# design.net
KiCad netlist of a schematic drawn in Altium Designer
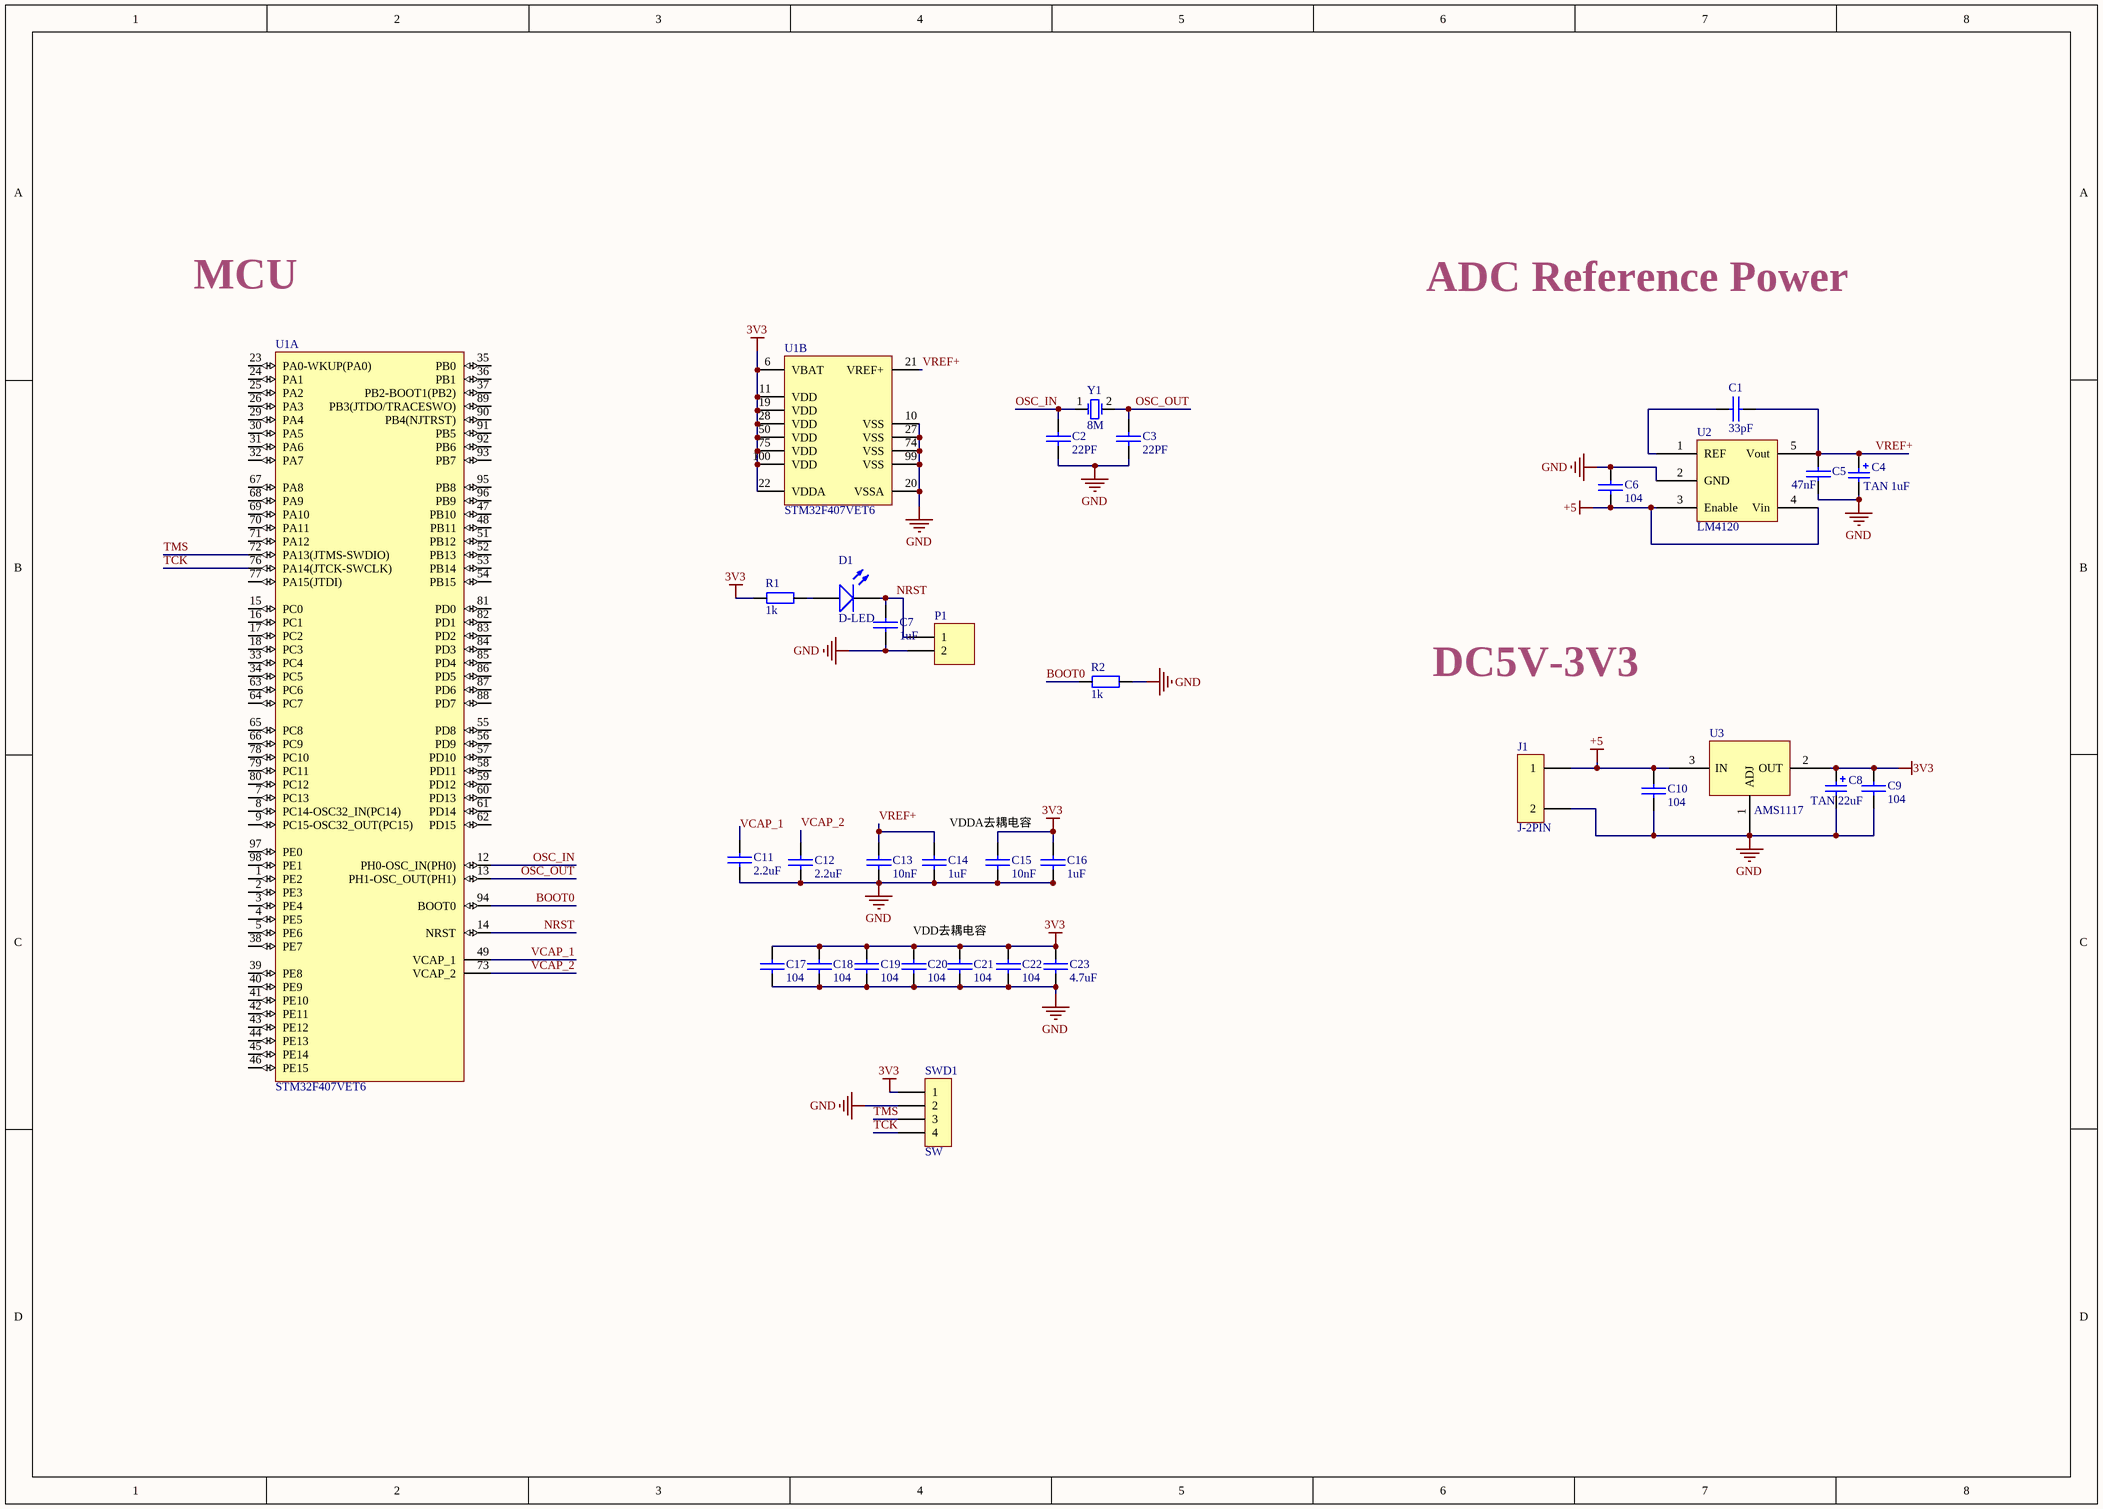
[diagram p0: 更新版.SchDoc]

(export (version "E")
  (design (tool "Eeschema 10.0.6"))
  (components
    (comp (ref "C1")
      (value "33pF")
      (footprint "C-0603")
      (description "MLCC")
      (libsource (lib "ACTION_SchematicDiagramPack") (part "C"))
    )
    (comp (ref "C2")
      (value "22PF")
      (footprint "C-0603")
      (description "MLCC")
      (libsource (lib "ACTION_SchematicDiagramPack") (part "C"))
    )
    (comp (ref "C3")
      (value "22PF")
      (footprint "C-0603")
      (description "MLCC")
      (libsource (lib "ACTION_SchematicDiagramPack") (part "C"))
    )
    (comp (ref "C4")
      (value "TAN 1uF")
      (footprint "CAP-Ta-1206")
      (description "Tantalum Capacitors")
      (libsource (lib "ACTION_SchematicDiagramPack") (part "C-TAN"))
    )
    (comp (ref "C5")
      (value "47nF")
      (footprint "C-0603")
      (description "MLCC")
      (libsource (lib "ACTION_SchematicDiagramPack") (part "C"))
    )
    (comp (ref "C6")
      (value "104")
      (footprint "C-0603")
      (description "MLCC")
      (libsource (lib "ACTION_SchematicDiagramPack") (part "C"))
    )
    (comp (ref "C7")
      (value "1uF")
      (footprint "C-0603")
      (description "MLCC")
      (libsource (lib "ACTION_SchematicDiagramPack") (part "C"))
    )
    (comp (ref "C8")
      (value "TAN 22uF")
      (footprint "CAP-Ta-1206")
      (description "Tantalum Capacitors")
      (libsource (lib "ACTION_SchematicDiagramPack") (part "C-TAN"))
    )
    (comp (ref "C9")
      (value "104")
      (footprint "C-0603")
      (description "MLCC")
      (libsource (lib "ACTION_SchematicDiagramPack") (part "C"))
    )
    (comp (ref "C10")
      (value "104")
      (footprint "C-0603")
      (description "MLCC")
      (libsource (lib "ACTION_SchematicDiagramPack") (part "C"))
    )
    (comp (ref "C11")
      (value "2.2uF")
      (footprint "C-0603")
      (description "MLCC")
      (libsource (lib "ACTION_SchematicDiagramPack") (part "C"))
    )
    (comp (ref "C12")
      (value "2.2uF")
      (footprint "C-0603")
      (description "MLCC")
      (libsource (lib "ACTION_SchematicDiagramPack") (part "C"))
    )
    (comp (ref "C13")
      (value "10nF")
      (footprint "C-0603")
      (description "MLCC")
      (libsource (lib "ACTION_SchematicDiagramPack") (part "C"))
    )
    (comp (ref "C14")
      (value "1uF")
      (footprint "C-0603")
      (description "MLCC")
      (libsource (lib "ACTION_SchematicDiagramPack") (part "C"))
    )
    (comp (ref "C15")
      (value "10nF")
      (footprint "C-0603")
      (description "MLCC")
      (libsource (lib "ACTION_SchematicDiagramPack") (part "C"))
    )
    (comp (ref "C16")
      (value "1uF")
      (footprint "C-0603")
      (description "MLCC")
      (libsource (lib "ACTION_SchematicDiagramPack") (part "C"))
    )
    (comp (ref "C17")
      (value "104")
      (footprint "C-0603")
      (description "MLCC")
      (libsource (lib "ACTION_SchematicDiagramPack") (part "C"))
    )
    (comp (ref "C18")
      (value "104")
      (footprint "C-0603")
      (description "MLCC")
      (libsource (lib "ACTION_SchematicDiagramPack") (part "C"))
    )
    (comp (ref "C19")
      (value "104")
      (footprint "C-0603")
      (description "MLCC")
      (libsource (lib "ACTION_SchematicDiagramPack") (part "C"))
    )
    (comp (ref "C20")
      (value "104")
      (footprint "C-0603")
      (description "MLCC")
      (libsource (lib "ACTION_SchematicDiagramPack") (part "C"))
    )
    (comp (ref "C21")
      (value "104")
      (footprint "C-0603")
      (description "MLCC")
      (libsource (lib "ACTION_SchematicDiagramPack") (part "C"))
    )
    (comp (ref "C22")
      (value "104")
      (footprint "C-0603")
      (description "MLCC")
      (libsource (lib "ACTION_SchematicDiagramPack") (part "C"))
    )
    (comp (ref "C23")
      (value "4.7uF")
      (footprint "C-0603")
      (description "MLCC")
      (libsource (lib "ACTION_SchematicDiagramPack") (part "C"))
    )
    (comp (ref "D1")
      (value "D-LED")
      (footprint "D-LED-0603")
      (description "LED")
      (libsource (lib "ACTION_SchematicDiagramPack") (part "D-LED"))
    )
    (comp (ref "J1")
      (value "J-2PIN")
      (footprint "J-XH-2A")
      (libsource (lib "ACTION_SchematicDiagramPack") (part "J-2PIN"))
    )
    (comp (ref "P1")
      (value "~")
      (footprint "按键两脚")
      (description "Header, 2-Pin")
      (fields (field (name "PUBLISHER") "Altium Limited"))
      (libsource (lib "Miscellaneous Connectors") (part "Header 2"))
    )
    (comp (ref "R1")
      (value "1k")
      (footprint "R-0603")
      (description "Resistor")
      (libsource (lib "ACTION_SchematicDiagramPack") (part "R"))
    )
    (comp (ref "R2")
      (value "1k")
      (footprint "R-0603")
      (description "Resistor")
      (libsource (lib "ACTION_SchematicDiagramPack") (part "R"))
    )
    (comp (ref "SWD1")
      (value "SW")
      (footprint "J-1.27-4P")
      (fields (field (name "PUBLISHER") "Altium Limited"))
      (libsource (lib "ACTION_SchematicDiagramPack") (part "J-4PIN"))
    )
    (comp (ref "U1")
      (value "STM32F407VET6")
      (footprint "STM-LQFP100_M")
      (libsource (lib "ACTION_SchematicDiagramPack") (part "STM32F407VET6"))
    )
    (comp (ref "U2")
      (value "LM4120")
      (footprint "SOT-235")
      (description "基准电压IC")
      (libsource (lib "ACTION_SchematicDiagramPack") (part "LM4120"))
    )
    (comp (ref "U3")
      (value "AMS1117")
      (footprint "SOT-223")
      (description "LDO")
      (libsource (lib "ACTION_SchematicDiagramPack") (part "AMS1117"))
    )
    (comp (ref "Y1")
      (value "8M")
      (footprint "X-HC49S")
      (description "Crystal Oscillator")
      (fields (field (name "PUBLISHER") "Altium Limited"))
      (libsource (lib "ACTION_SchematicDiagramPack") (part "Crystal"))
    )
  )
  (nets
    (net (code "1") (name "+5") (class "Default")
      (node (ref "C10") (pin "1") (pinfunction "1_1") (pintype "passive"))
      (node (ref "C6") (pin "2") (pinfunction "2_2") (pintype "passive"))
      (node (ref "J1") (pin "1") (pinfunction "1_1") (pintype "passive"))
      (node (ref "U2") (pin "3") (pinfunction "Enable_3") (pintype "passive"))
      (node (ref "U2") (pin "4") (pinfunction "Vin_4") (pintype "passive"))
      (node (ref "U3") (pin "3") (pinfunction "IN_3") (pintype "passive"))
    )
    (net (code "2") (name "/BOOT0") (class "Default")
      (node (ref "R2") (pin "1") (pintype "passive"))
      (node (ref "U1") (pin "94") (pinfunction "BOOT0_94") (pintype "bidirectional"))
    )
    (net (code "3") (name "/NRST") (class "Default")
      (node (ref "C7") (pin "2") (pinfunction "2_2") (pintype "passive"))
      (node (ref "D1") (pin "K") (pinfunction "K_K") (pintype "passive"))
      (node (ref "P1") (pin "1") (pinfunction "1_1") (pintype "passive"))
      (node (ref "U1") (pin "14") (pinfunction "NRST_14") (pintype "bidirectional"))
    )
    (net (code "4") (name "/OSC_IN") (class "Default")
      (node (ref "C2") (pin "1") (pinfunction "1_1") (pintype "passive"))
      (node (ref "U1") (pin "12") (pinfunction "PH0-OSC_IN(PH0)_12") (pintype "bidirectional"))
      (node (ref "Y1") (pin "1") (pinfunction "OSC1_1") (pintype "passive"))
    )
    (net (code "5") (name "/OSC_OUT") (class "Default")
      (node (ref "C3") (pin "1") (pinfunction "1_1") (pintype "passive"))
      (node (ref "U1") (pin "13") (pinfunction "PH1-OSC_OUT(PH1)_13") (pintype "bidirectional"))
      (node (ref "Y1") (pin "2") (pinfunction "OSC2_2") (pintype "passive"))
    )
    (net (code "6") (name "/TCK") (class "Default")
      (node (ref "SWD1") (pin "4") (pinfunction "4_4") (pintype "passive"))
      (node (ref "U1") (pin "76") (pinfunction "PA14(JTCK-SWCLK)_76") (pintype "bidirectional"))
    )
    (net (code "7") (name "/TMS") (class "Default")
      (node (ref "SWD1") (pin "3") (pinfunction "3_3") (pintype "passive"))
      (node (ref "U1") (pin "72") (pinfunction "PA13(JTMS-SWDIO)_72") (pintype "bidirectional"))
    )
    (net (code "8") (name "/VCAP_1") (class "Default")
      (node (ref "C11") (pin "2") (pinfunction "2_2") (pintype "passive"))
      (node (ref "U1") (pin "49") (pinfunction "VCAP_1_49") (pintype "power_in"))
    )
    (net (code "9") (name "/VCAP_2") (class "Default")
      (node (ref "C12") (pin "2") (pinfunction "2_2") (pintype "passive"))
      (node (ref "U1") (pin "73") (pinfunction "VCAP_2_73") (pintype "power_in"))
    )
    (net (code "10") (name "/VREF+") (class "Default")
      (node (ref "C1") (pin "2") (pinfunction "2_2") (pintype "passive"))
      (node (ref "C13") (pin "2") (pinfunction "2_2") (pintype "passive"))
      (node (ref "C14") (pin "2") (pinfunction "2_2") (pintype "passive"))
      (node (ref "C4") (pin "1") (pinfunction "1_1") (pintype "passive"))
      (node (ref "C5") (pin "1") (pinfunction "1_1") (pintype "passive"))
      (node (ref "U1") (pin "21") (pinfunction "VREF+_21") (pintype "power_in"))
      (node (ref "U2") (pin "5") (pinfunction "Vout_5") (pintype "passive"))
    )
    (net (code "11") (name "3V3") (class "Default")
      (node (ref "C15") (pin "2") (pinfunction "2_2") (pintype "passive"))
      (node (ref "C16") (pin "2") (pinfunction "2_2") (pintype "passive"))
      (node (ref "C17") (pin "2") (pinfunction "2_2") (pintype "passive"))
      (node (ref "C18") (pin "2") (pinfunction "2_2") (pintype "passive"))
      (node (ref "C19") (pin "2") (pinfunction "2_2") (pintype "passive"))
      (node (ref "C20") (pin "2") (pinfunction "2_2") (pintype "passive"))
      (node (ref "C21") (pin "2") (pinfunction "2_2") (pintype "passive"))
      (node (ref "C22") (pin "2") (pinfunction "2_2") (pintype "passive"))
      (node (ref "C23") (pin "2") (pinfunction "2_2") (pintype "passive"))
      (node (ref "C8") (pin "1") (pinfunction "1_1") (pintype "passive"))
      (node (ref "C9") (pin "1") (pinfunction "1_1") (pintype "passive"))
      (node (ref "R1") (pin "1") (pintype "passive"))
      (node (ref "SWD1") (pin "1") (pinfunction "1_1") (pintype "passive"))
      (node (ref "U1") (pin "100") (pinfunction "VDD_100") (pintype "power_in"))
      (node (ref "U1") (pin "11") (pinfunction "VDD_11") (pintype "power_in"))
      (node (ref "U1") (pin "19") (pinfunction "VDD_19") (pintype "power_in"))
      (node (ref "U1") (pin "22") (pinfunction "VDDA_22") (pintype "power_in"))
      (node (ref "U1") (pin "28") (pinfunction "VDD_28") (pintype "power_in"))
      (node (ref "U1") (pin "50") (pinfunction "VDD_50") (pintype "power_in"))
      (node (ref "U1") (pin "6") (pinfunction "VBAT_6") (pintype "power_in"))
      (node (ref "U1") (pin "75") (pinfunction "VDD_75") (pintype "power_in"))
      (node (ref "U3") (pin "2") (pinfunction "OUT_2") (pintype "passive"))
    )
    (net (code "12") (name "GND") (class "Default")
      (node (ref "C10") (pin "2") (pinfunction "2_2") (pintype "passive"))
      (node (ref "C11") (pin "1") (pinfunction "1_1") (pintype "passive"))
      (node (ref "C12") (pin "1") (pinfunction "1_1") (pintype "passive"))
      (node (ref "C13") (pin "1") (pinfunction "1_1") (pintype "passive"))
      (node (ref "C14") (pin "1") (pinfunction "1_1") (pintype "passive"))
      (node (ref "C15") (pin "1") (pinfunction "1_1") (pintype "passive"))
      (node (ref "C16") (pin "1") (pinfunction "1_1") (pintype "passive"))
      (node (ref "C17") (pin "1") (pinfunction "1_1") (pintype "passive"))
      (node (ref "C18") (pin "1") (pinfunction "1_1") (pintype "passive"))
      (node (ref "C19") (pin "1") (pinfunction "1_1") (pintype "passive"))
      (node (ref "C2") (pin "2") (pinfunction "2_2") (pintype "passive"))
      (node (ref "C20") (pin "1") (pinfunction "1_1") (pintype "passive"))
      (node (ref "C21") (pin "1") (pinfunction "1_1") (pintype "passive"))
      (node (ref "C22") (pin "1") (pinfunction "1_1") (pintype "passive"))
      (node (ref "C23") (pin "1") (pinfunction "1_1") (pintype "passive"))
      (node (ref "C3") (pin "2") (pinfunction "2_2") (pintype "passive"))
      (node (ref "C4") (pin "2") (pinfunction "2_2") (pintype "passive"))
      (node (ref "C5") (pin "2") (pinfunction "2_2") (pintype "passive"))
      (node (ref "C6") (pin "1") (pinfunction "1_1") (pintype "passive"))
      (node (ref "C7") (pin "1") (pinfunction "1_1") (pintype "passive"))
      (node (ref "C8") (pin "2") (pinfunction "2_2") (pintype "passive"))
      (node (ref "C9") (pin "2") (pinfunction "2_2") (pintype "passive"))
      (node (ref "J1") (pin "2") (pinfunction "2_2") (pintype "passive"))
      (node (ref "P1") (pin "2") (pinfunction "2_2") (pintype "passive"))
      (node (ref "R2") (pin "2") (pintype "passive"))
      (node (ref "SWD1") (pin "2") (pinfunction "2_2") (pintype "passive"))
      (node (ref "U1") (pin "10") (pinfunction "VSS_10") (pintype "power_in"))
      (node (ref "U1") (pin "20") (pinfunction "VSSA_20") (pintype "power_in"))
      (node (ref "U1") (pin "27") (pinfunction "VSS_27") (pintype "power_in"))
      (node (ref "U1") (pin "74") (pinfunction "VSS_74") (pintype "power_in"))
      (node (ref "U1") (pin "99") (pinfunction "VSS_99") (pintype "power_in"))
      (node (ref "U2") (pin "2") (pinfunction "GND_2") (pintype "passive"))
      (node (ref "U3") (pin "1") (pinfunction "ADJ_1") (pintype "passive"))
    )
    (net (code "13") (name "Net-(D1-PadA)") (class "Default")
      (node (ref "D1") (pin "A") (pinfunction "A_A") (pintype "passive"))
      (node (ref "R1") (pin "2") (pintype "passive"))
    )
    (net (code "14") (name "Net-(U2-REF)") (class "Default")
      (node (ref "C1") (pin "1") (pinfunction "1_1") (pintype "passive"))
      (node (ref "U2") (pin "1") (pinfunction "REF_1") (pintype "passive"))
    )
    (net (code "15") (name "unconnected-(U1A-PA0-WKUP(PA0)-Pad23)") (class "Default")
      (node (ref "U1") (pin "23") (pinfunction "PA0-WKUP(PA0)_23") (pintype "bidirectional"))
    )
    (net (code "16") (name "unconnected-(U1A-PA1-Pad24)") (class "Default")
      (node (ref "U1") (pin "24") (pinfunction "PA1_24") (pintype "bidirectional"))
    )
    (net (code "17") (name "unconnected-(U1A-PA2-Pad25)") (class "Default")
      (node (ref "U1") (pin "25") (pinfunction "PA2_25") (pintype "bidirectional"))
    )
    (net (code "18") (name "unconnected-(U1A-PA3-Pad26)") (class "Default")
      (node (ref "U1") (pin "26") (pinfunction "PA3_26") (pintype "bidirectional"))
    )
    (net (code "19") (name "unconnected-(U1A-PA4-Pad29)") (class "Default")
      (node (ref "U1") (pin "29") (pinfunction "PA4_29") (pintype "bidirectional"))
    )
    (net (code "20") (name "unconnected-(U1A-PA5-Pad30)") (class "Default")
      (node (ref "U1") (pin "30") (pinfunction "PA5_30") (pintype "bidirectional"))
    )
    (net (code "21") (name "unconnected-(U1A-PA6-Pad31)") (class "Default")
      (node (ref "U1") (pin "31") (pinfunction "PA6_31") (pintype "bidirectional"))
    )
    (net (code "22") (name "unconnected-(U1A-PA7-Pad32)") (class "Default")
      (node (ref "U1") (pin "32") (pinfunction "PA7_32") (pintype "bidirectional"))
    )
    (net (code "23") (name "unconnected-(U1A-PA8-Pad67)") (class "Default")
      (node (ref "U1") (pin "67") (pinfunction "PA8_67") (pintype "bidirectional"))
    )
    (net (code "24") (name "unconnected-(U1A-PA9-Pad68)") (class "Default")
      (node (ref "U1") (pin "68") (pinfunction "PA9_68") (pintype "bidirectional"))
    )
    (net (code "25") (name "unconnected-(U1A-PA10-Pad69)") (class "Default")
      (node (ref "U1") (pin "69") (pinfunction "PA10_69") (pintype "bidirectional"))
    )
    (net (code "26") (name "unconnected-(U1A-PA11-Pad70)") (class "Default")
      (node (ref "U1") (pin "70") (pinfunction "PA11_70") (pintype "bidirectional"))
    )
    (net (code "27") (name "unconnected-(U1A-PA12-Pad71)") (class "Default")
      (node (ref "U1") (pin "71") (pinfunction "PA12_71") (pintype "bidirectional"))
    )
    (net (code "28") (name "unconnected-(U1A-PA15(JTDI)-Pad77)") (class "Default")
      (node (ref "U1") (pin "77") (pinfunction "PA15(JTDI)_77") (pintype "bidirectional"))
    )
    (net (code "29") (name "unconnected-(U1A-PB0-Pad35)") (class "Default")
      (node (ref "U1") (pin "35") (pinfunction "PB0_35") (pintype "bidirectional"))
    )
    (net (code "30") (name "unconnected-(U1A-PB1-Pad36)") (class "Default")
      (node (ref "U1") (pin "36") (pinfunction "PB1_36") (pintype "bidirectional"))
    )
    (net (code "31") (name "unconnected-(U1A-PB2-BOOT1(PB2)-Pad37)") (class "Default")
      (node (ref "U1") (pin "37") (pinfunction "PB2-BOOT1(PB2)_37") (pintype "bidirectional"))
    )
    (net (code "32") (name "unconnected-(U1A-PB3(JTDO{slash}TRACESWO)-Pad89)") (class "Default")
      (node (ref "U1") (pin "89") (pinfunction "PB3(JTDO/TRACESWO)_89") (pintype "bidirectional"))
    )
    (net (code "33") (name "unconnected-(U1A-PB4(NJTRST)-Pad90)") (class "Default")
      (node (ref "U1") (pin "90") (pinfunction "PB4(NJTRST)_90") (pintype "bidirectional"))
    )
    (net (code "34") (name "unconnected-(U1A-PB5-Pad91)") (class "Default")
      (node (ref "U1") (pin "91") (pinfunction "PB5_91") (pintype "bidirectional"))
    )
    (net (code "35") (name "unconnected-(U1A-PB6-Pad92)") (class "Default")
      (node (ref "U1") (pin "92") (pinfunction "PB6_92") (pintype "bidirectional"))
    )
    (net (code "36") (name "unconnected-(U1A-PB7-Pad93)") (class "Default")
      (node (ref "U1") (pin "93") (pinfunction "PB7_93") (pintype "bidirectional"))
    )
    (net (code "37") (name "unconnected-(U1A-PB8-Pad95)") (class "Default")
      (node (ref "U1") (pin "95") (pinfunction "PB8_95") (pintype "bidirectional"))
    )
    (net (code "38") (name "unconnected-(U1A-PB9-Pad96)") (class "Default")
      (node (ref "U1") (pin "96") (pinfunction "PB9_96") (pintype "bidirectional"))
    )
    (net (code "39") (name "unconnected-(U1A-PB10-Pad47)") (class "Default")
      (node (ref "U1") (pin "47") (pinfunction "PB10_47") (pintype "bidirectional"))
    )
    (net (code "40") (name "unconnected-(U1A-PB11-Pad48)") (class "Default")
      (node (ref "U1") (pin "48") (pinfunction "PB11_48") (pintype "bidirectional"))
    )
    (net (code "41") (name "unconnected-(U1A-PB12-Pad51)") (class "Default")
      (node (ref "U1") (pin "51") (pinfunction "PB12_51") (pintype "bidirectional"))
    )
    (net (code "42") (name "unconnected-(U1A-PB13-Pad52)") (class "Default")
      (node (ref "U1") (pin "52") (pinfunction "PB13_52") (pintype "bidirectional"))
    )
    (net (code "43") (name "unconnected-(U1A-PB14-Pad53)") (class "Default")
      (node (ref "U1") (pin "53") (pinfunction "PB14_53") (pintype "bidirectional"))
    )
    (net (code "44") (name "unconnected-(U1A-PB15-Pad54)") (class "Default")
      (node (ref "U1") (pin "54") (pinfunction "PB15_54") (pintype "bidirectional"))
    )
    (net (code "45") (name "unconnected-(U1A-PC0-Pad15)") (class "Default")
      (node (ref "U1") (pin "15") (pinfunction "PC0_15") (pintype "bidirectional"))
    )
    (net (code "46") (name "unconnected-(U1A-PC1-Pad16)") (class "Default")
      (node (ref "U1") (pin "16") (pinfunction "PC1_16") (pintype "bidirectional"))
    )
    (net (code "47") (name "unconnected-(U1A-PC2-Pad17)") (class "Default")
      (node (ref "U1") (pin "17") (pinfunction "PC2_17") (pintype "bidirectional"))
    )
    (net (code "48") (name "unconnected-(U1A-PC3-Pad18)") (class "Default")
      (node (ref "U1") (pin "18") (pinfunction "PC3_18") (pintype "bidirectional"))
    )
    (net (code "49") (name "unconnected-(U1A-PC4-Pad33)") (class "Default")
      (node (ref "U1") (pin "33") (pinfunction "PC4_33") (pintype "bidirectional"))
    )
    (net (code "50") (name "unconnected-(U1A-PC5-Pad34)") (class "Default")
      (node (ref "U1") (pin "34") (pinfunction "PC5_34") (pintype "bidirectional"))
    )
    (net (code "51") (name "unconnected-(U1A-PC6-Pad63)") (class "Default")
      (node (ref "U1") (pin "63") (pinfunction "PC6_63") (pintype "bidirectional"))
    )
    (net (code "52") (name "unconnected-(U1A-PC7-Pad64)") (class "Default")
      (node (ref "U1") (pin "64") (pinfunction "PC7_64") (pintype "bidirectional"))
    )
    (net (code "53") (name "unconnected-(U1A-PC8-Pad65)") (class "Default")
      (node (ref "U1") (pin "65") (pinfunction "PC8_65") (pintype "bidirectional"))
    )
    (net (code "54") (name "unconnected-(U1A-PC9-Pad66)") (class "Default")
      (node (ref "U1") (pin "66") (pinfunction "PC9_66") (pintype "bidirectional"))
    )
    (net (code "55") (name "unconnected-(U1A-PC10-Pad78)") (class "Default")
      (node (ref "U1") (pin "78") (pinfunction "PC10_78") (pintype "bidirectional"))
    )
    (net (code "56") (name "unconnected-(U1A-PC11-Pad79)") (class "Default")
      (node (ref "U1") (pin "79") (pinfunction "PC11_79") (pintype "bidirectional"))
    )
    (net (code "57") (name "unconnected-(U1A-PC12-Pad80)") (class "Default")
      (node (ref "U1") (pin "80") (pinfunction "PC12_80") (pintype "bidirectional"))
    )
    (net (code "58") (name "unconnected-(U1A-PC13-Pad7)") (class "Default")
      (node (ref "U1") (pin "7") (pinfunction "PC13_7") (pintype "bidirectional"))
    )
    (net (code "59") (name "unconnected-(U1A-PC14-OSC32_IN(PC14)-Pad8)") (class "Default")
      (node (ref "U1") (pin "8") (pinfunction "PC14-OSC32_IN(PC14)_8") (pintype "bidirectional"))
    )
    (net (code "60") (name "unconnected-(U1A-PC15-OSC32_OUT(PC15)-Pad9)") (class "Default")
      (node (ref "U1") (pin "9") (pinfunction "PC15-OSC32_OUT(PC15)_9") (pintype "bidirectional"))
    )
    (net (code "61") (name "unconnected-(U1A-PD0-Pad81)") (class "Default")
      (node (ref "U1") (pin "81") (pinfunction "PD0_81") (pintype "bidirectional"))
    )
    (net (code "62") (name "unconnected-(U1A-PD1-Pad82)") (class "Default")
      (node (ref "U1") (pin "82") (pinfunction "PD1_82") (pintype "bidirectional"))
    )
    (net (code "63") (name "unconnected-(U1A-PD2-Pad83)") (class "Default")
      (node (ref "U1") (pin "83") (pinfunction "PD2_83") (pintype "bidirectional"))
    )
    (net (code "64") (name "unconnected-(U1A-PD3-Pad84)") (class "Default")
      (node (ref "U1") (pin "84") (pinfunction "PD3_84") (pintype "bidirectional"))
    )
    (net (code "65") (name "unconnected-(U1A-PD4-Pad85)") (class "Default")
      (node (ref "U1") (pin "85") (pinfunction "PD4_85") (pintype "bidirectional"))
    )
    (net (code "66") (name "unconnected-(U1A-PD5-Pad86)") (class "Default")
      (node (ref "U1") (pin "86") (pinfunction "PD5_86") (pintype "bidirectional"))
    )
    (net (code "67") (name "unconnected-(U1A-PD6-Pad87)") (class "Default")
      (node (ref "U1") (pin "87") (pinfunction "PD6_87") (pintype "bidirectional"))
    )
    (net (code "68") (name "unconnected-(U1A-PD7-Pad88)") (class "Default")
      (node (ref "U1") (pin "88") (pinfunction "PD7_88") (pintype "bidirectional"))
    )
    (net (code "69") (name "unconnected-(U1A-PD8-Pad55)") (class "Default")
      (node (ref "U1") (pin "55") (pinfunction "PD8_55") (pintype "bidirectional"))
    )
    (net (code "70") (name "unconnected-(U1A-PD9-Pad56)") (class "Default")
      (node (ref "U1") (pin "56") (pinfunction "PD9_56") (pintype "bidirectional"))
    )
    (net (code "71") (name "unconnected-(U1A-PD10-Pad57)") (class "Default")
      (node (ref "U1") (pin "57") (pinfunction "PD10_57") (pintype "bidirectional"))
    )
    (net (code "72") (name "unconnected-(U1A-PD11-Pad58)") (class "Default")
      (node (ref "U1") (pin "58") (pinfunction "PD11_58") (pintype "bidirectional"))
    )
    (net (code "73") (name "unconnected-(U1A-PD12-Pad59)") (class "Default")
      (node (ref "U1") (pin "59") (pinfunction "PD12_59") (pintype "bidirectional"))
    )
    (net (code "74") (name "unconnected-(U1A-PD13-Pad60)") (class "Default")
      (node (ref "U1") (pin "60") (pinfunction "PD13_60") (pintype "bidirectional"))
    )
    (net (code "75") (name "unconnected-(U1A-PD14-Pad61)") (class "Default")
      (node (ref "U1") (pin "61") (pinfunction "PD14_61") (pintype "bidirectional"))
    )
    (net (code "76") (name "unconnected-(U1A-PD15-Pad62)") (class "Default")
      (node (ref "U1") (pin "62") (pinfunction "PD15_62") (pintype "bidirectional"))
    )
    (net (code "77") (name "unconnected-(U1A-PE0-Pad97)") (class "Default")
      (node (ref "U1") (pin "97") (pinfunction "PE0_97") (pintype "bidirectional"))
    )
    (net (code "78") (name "unconnected-(U1A-PE1-Pad98)") (class "Default")
      (node (ref "U1") (pin "98") (pinfunction "PE1_98") (pintype "bidirectional"))
    )
    (net (code "79") (name "unconnected-(U1A-PE2-Pad1)") (class "Default")
      (node (ref "U1") (pin "1") (pinfunction "PE2_1") (pintype "bidirectional"))
    )
    (net (code "80") (name "unconnected-(U1A-PE3-Pad2)") (class "Default")
      (node (ref "U1") (pin "2") (pinfunction "PE3_2") (pintype "bidirectional"))
    )
    (net (code "81") (name "unconnected-(U1A-PE4-Pad3)") (class "Default")
      (node (ref "U1") (pin "3") (pinfunction "PE4_3") (pintype "bidirectional"))
    )
    (net (code "82") (name "unconnected-(U1A-PE5-Pad4)") (class "Default")
      (node (ref "U1") (pin "4") (pinfunction "PE5_4") (pintype "bidirectional"))
    )
    (net (code "83") (name "unconnected-(U1A-PE6-Pad5)") (class "Default")
      (node (ref "U1") (pin "5") (pinfunction "PE6_5") (pintype "bidirectional"))
    )
    (net (code "84") (name "unconnected-(U1A-PE7-Pad38)") (class "Default")
      (node (ref "U1") (pin "38") (pinfunction "PE7_38") (pintype "bidirectional"))
    )
    (net (code "85") (name "unconnected-(U1A-PE8-Pad39)") (class "Default")
      (node (ref "U1") (pin "39") (pinfunction "PE8_39") (pintype "bidirectional"))
    )
    (net (code "86") (name "unconnected-(U1A-PE9-Pad40)") (class "Default")
      (node (ref "U1") (pin "40") (pinfunction "PE9_40") (pintype "bidirectional"))
    )
    (net (code "87") (name "unconnected-(U1A-PE10-Pad41)") (class "Default")
      (node (ref "U1") (pin "41") (pinfunction "PE10_41") (pintype "bidirectional"))
    )
    (net (code "88") (name "unconnected-(U1A-PE11-Pad42)") (class "Default")
      (node (ref "U1") (pin "42") (pinfunction "PE11_42") (pintype "bidirectional"))
    )
    (net (code "89") (name "unconnected-(U1A-PE12-Pad43)") (class "Default")
      (node (ref "U1") (pin "43") (pinfunction "PE12_43") (pintype "bidirectional"))
    )
    (net (code "90") (name "unconnected-(U1A-PE13-Pad44)") (class "Default")
      (node (ref "U1") (pin "44") (pinfunction "PE13_44") (pintype "bidirectional"))
    )
    (net (code "91") (name "unconnected-(U1A-PE14-Pad45)") (class "Default")
      (node (ref "U1") (pin "45") (pinfunction "PE14_45") (pintype "bidirectional"))
    )
    (net (code "92") (name "unconnected-(U1A-PE15-Pad46)") (class "Default")
      (node (ref "U1") (pin "46") (pinfunction "PE15_46") (pintype "bidirectional"))
    )
  )
)
